# Micro.net
KiCad netlist of a schematic drawn in Altium Designer
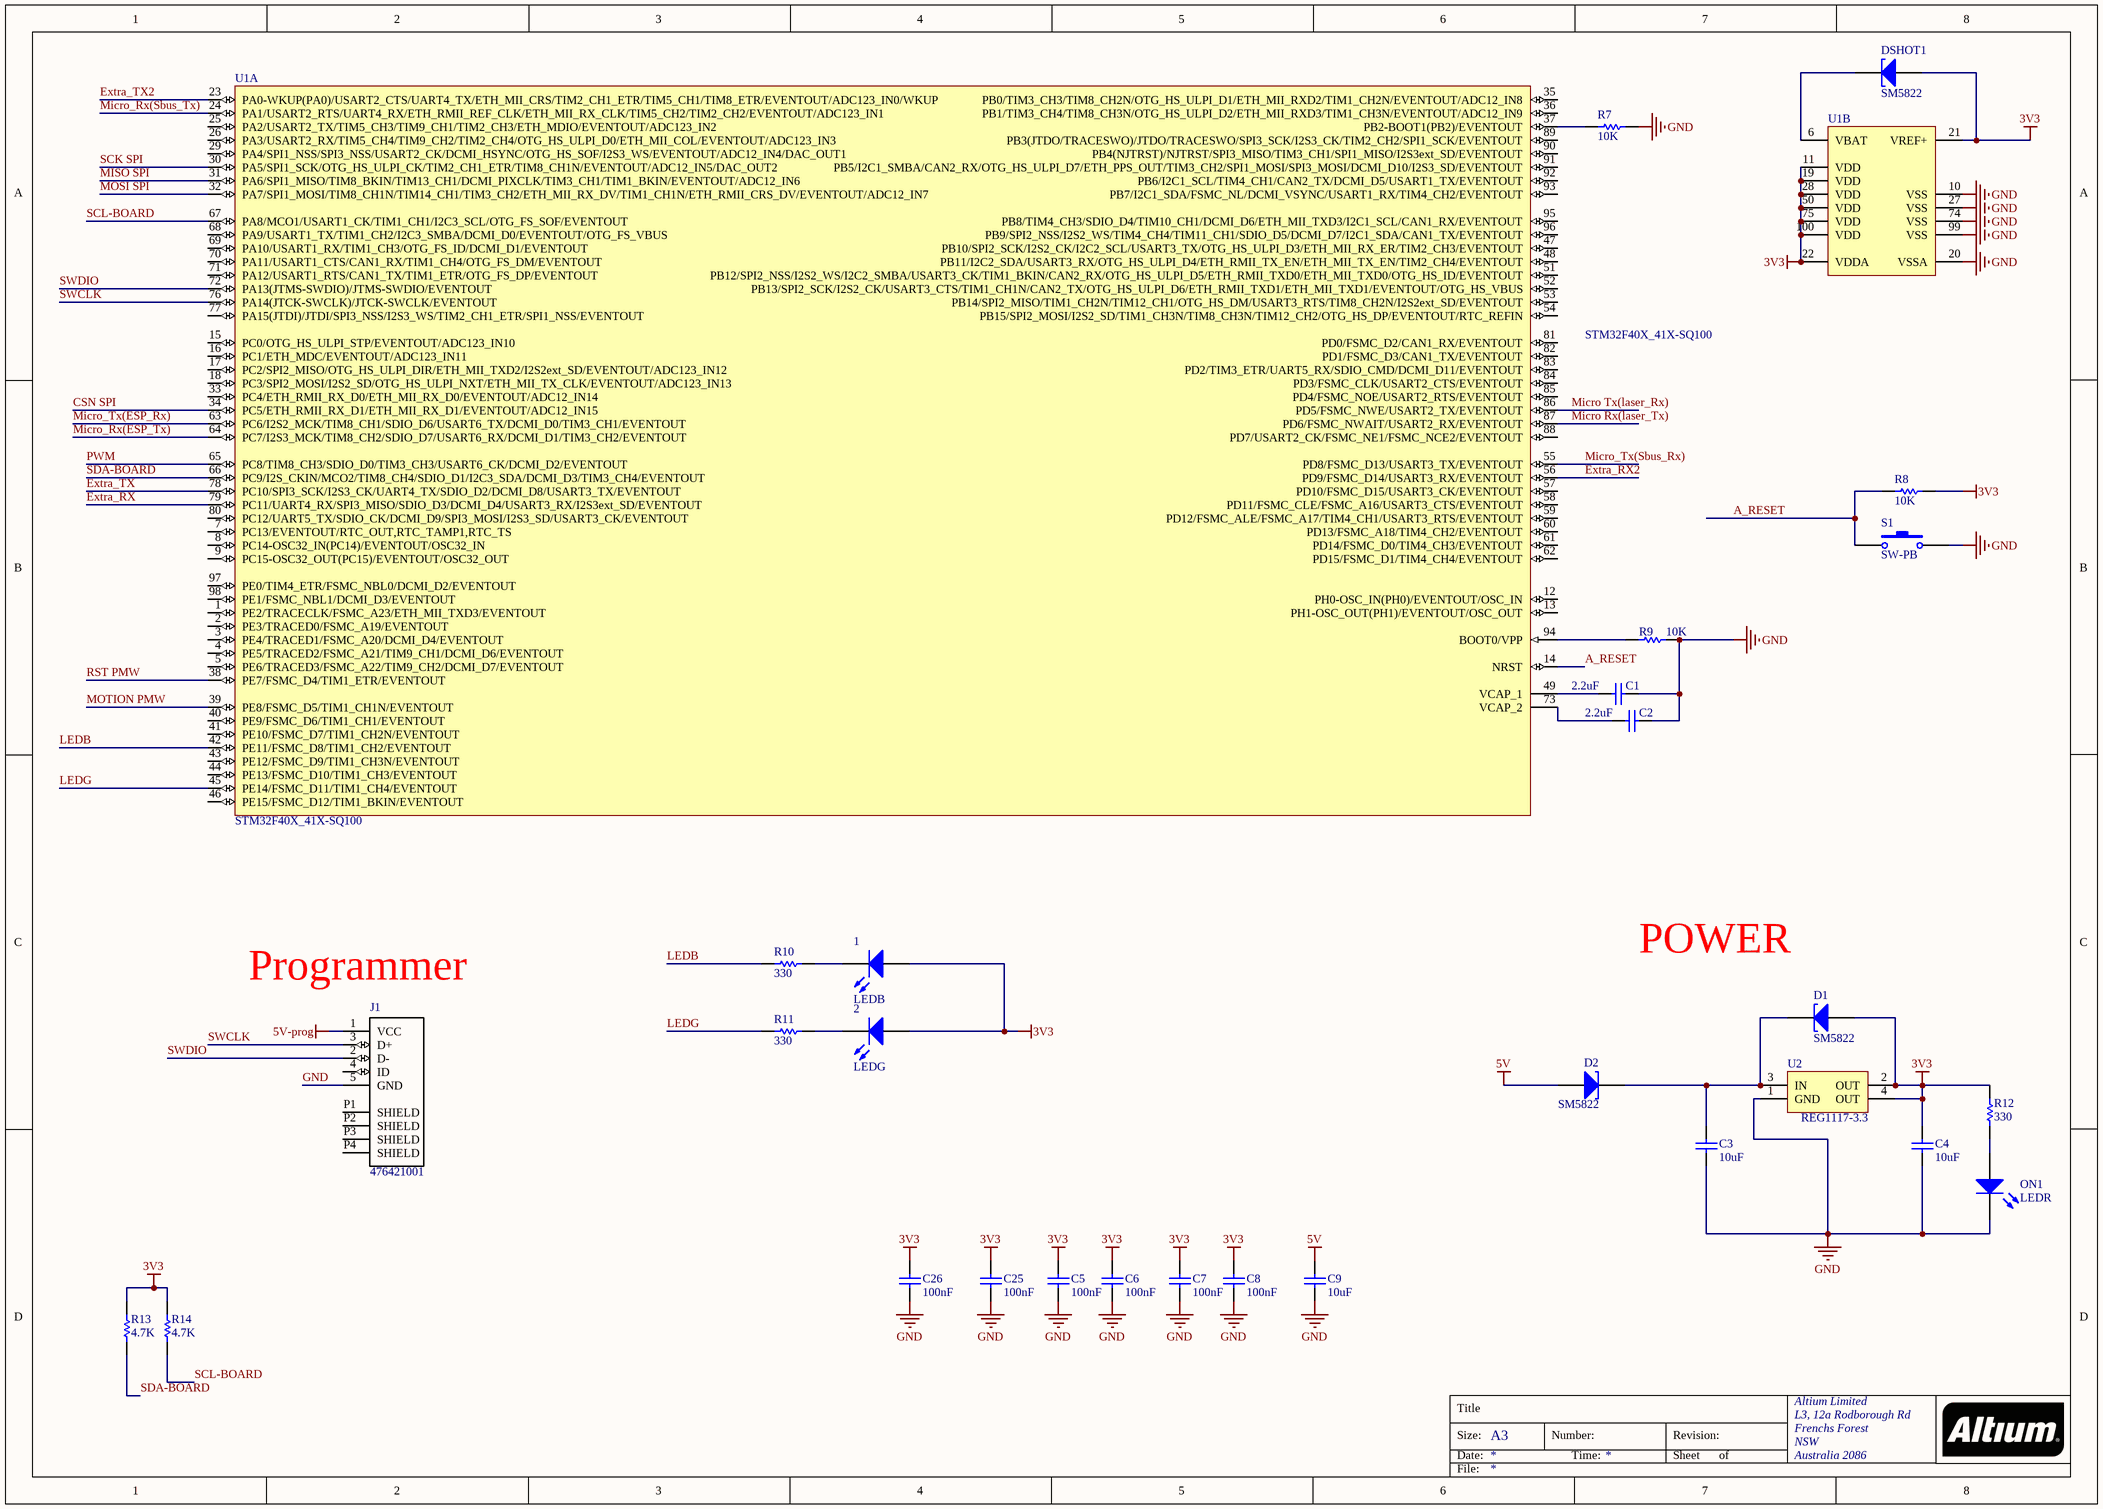
[diagram p0: Micro.SchDoc]

(export (version "E")
  (design (tool "Eeschema 10.0.6"))
  (components
    (comp (ref "1")
      (value "LEDB")
      (footprint "3518")
      (description "Typical INFRARED GaAs LED")
      (fields (field (name "PUBLISHER") "Altium Limited"))
      (libsource (lib "Miscellaneous Devices") (part "LED0"))
    )
    (comp (ref "2")
      (value "LEDG")
      (footprint "3518")
      (description "Typical INFRARED GaAs LED")
      (fields (field (name "PUBLISHER") "Altium Limited"))
      (libsource (lib "Miscellaneous Devices") (part "LED0"))
    )
    (comp (ref "C1")
      (value "2.2uF")
      (footprint "j1-0603")
      (description "Capacitor")
      (fields (field (name "PUBLISHER") "Altium Limited"))
      (libsource (lib "KN2CLib") (part "Cap_UP"))
    )
    (comp (ref "C2")
      (value "2.2uF")
      (footprint "j1-0603")
      (description "Capacitor")
      (fields (field (name "PUBLISHER") "Altium Limited"))
      (libsource (lib "KN2CLib") (part "Cap_UP"))
    )
    (comp (ref "C3")
      (value "10uF")
      (footprint "J1-0603")
      (description "Capacitor")
      (fields (field (name "PUBLISHER") "Altium Limited"))
      (libsource (lib "Miscellaneous Devices") (part "Cap"))
    )
    (comp (ref "C4")
      (value "10uF")
      (footprint "J1-0603")
      (description "Capacitor")
      (fields (field (name "PUBLISHER") "Altium Limited"))
      (libsource (lib "Miscellaneous Devices") (part "Cap"))
    )
    (comp (ref "C5")
      (value "100nF")
      (footprint "j1-0603")
      (description "Capacitor")
      (fields (field (name "PUBLISHER") "Altium Limited"))
      (libsource (lib "Miscellaneous Devices") (part "Cap"))
    )
    (comp (ref "C6")
      (value "100nF")
      (footprint "J1-0603")
      (description "Capacitor")
      (fields (field (name "PUBLISHER") "Altium Limited"))
      (libsource (lib "Miscellaneous Devices") (part "Cap"))
    )
    (comp (ref "C7")
      (value "100nF")
      (footprint "j1-0603")
      (description "Capacitor")
      (fields (field (name "PUBLISHER") "Altium Limited"))
      (libsource (lib "Miscellaneous Devices") (part "Cap"))
    )
    (comp (ref "C8")
      (value "100nF")
      (footprint "J1-0603")
      (description "Capacitor")
      (fields (field (name "PUBLISHER") "Altium Limited"))
      (libsource (lib "Miscellaneous Devices") (part "Cap"))
    )
    (comp (ref "C9")
      (value "10uF")
      (footprint "j1-0603")
      (description "Capacitor")
      (fields (field (name "PUBLISHER") "Altium Limited"))
      (libsource (lib "Miscellaneous Devices") (part "Cap"))
    )
    (comp (ref "C25")
      (value "100nF")
      (footprint "j1-0603")
      (description "Capacitor")
      (fields (field (name "PUBLISHER") "Altium Limited"))
      (libsource (lib "Miscellaneous Devices") (part "Cap"))
    )
    (comp (ref "C26")
      (value "100nF")
      (footprint "j1-0603")
      (description "Capacitor")
      (fields (field (name "PUBLISHER") "Altium Limited"))
      (libsource (lib "Miscellaneous Devices") (part "Cap"))
    )
    (comp (ref "D1")
      (value "SM5822")
      (footprint "US1M")
      (description "1 Amp General Purpose Rectifier")
      (fields (field (name "PUBLISHER") "Altium Limited"))
      (libsource (lib "KN2CLib") (part "Diode_ShotKey"))
    )
    (comp (ref "D2")
      (value "SM5822")
      (footprint "US1M")
      (description "1 Amp General Purpose Rectifier")
      (fields (field (name "PUBLISHER") "Altium Limited"))
      (libsource (lib "KN2CLib") (part "Diode_ShotKey"))
    )
    (comp (ref "DSHOT1")
      (value "SM5822")
      (footprint "US1M")
      (description "1 Amp General Purpose Rectifier")
      (fields (field (name "PUBLISHER") "Altium Limited"))
      (libsource (lib "KN2CLib") (part "Diode_ShotKey"))
    )
    (comp (ref "J1")
      (value "476421001")
      (footprint "*MOLEX_476421001_476421001(Primary)")
      (fields (field (name "MF") "Molex"))
      (libsource (lib "476421001") (part "476421001"))
    )
    (comp (ref "ON1")
      (value "LEDR")
      (footprint "3518")
      (description "Typical INFRARED GaAs LED")
      (fields (field (name "PUBLISHER") "Altium Limited"))
      (libsource (lib "Miscellaneous Devices") (part "LED0"))
    )
    (comp (ref "R7")
      (value "10K")
      (footprint "j1-0603")
      (description "Resistor")
      (fields (field (name "PUBLISHER") "Altium Limited"))
      (libsource (lib "Miscellaneous Devices") (part "Res1"))
    )
    (comp (ref "R8")
      (value "10K")
      (footprint "j1-0603")
      (description "Resistor")
      (fields (field (name "PUBLISHER") "Altium Limited"))
      (libsource (lib "Miscellaneous Devices") (part "Res1"))
    )
    (comp (ref "R9")
      (value "10K")
      (footprint "j1-0603")
      (description "Semiconductor Resistor")
      (fields (field (name "PUBLISHER") "Altium Limited"))
      (libsource (lib "KN2CLib") (part "Res"))
    )
    (comp (ref "R10")
      (value "330")
      (footprint "j1-0603")
      (description "Resistor")
      (fields (field (name "PUBLISHER") "Altium Limited"))
      (libsource (lib "Miscellaneous Devices") (part "Res1"))
    )
    (comp (ref "R11")
      (value "330")
      (footprint "j1-0603")
      (description "Resistor")
      (fields (field (name "PUBLISHER") "Altium Limited"))
      (libsource (lib "Miscellaneous Devices") (part "Res1"))
    )
    (comp (ref "R12")
      (value "330")
      (footprint "J1-0603")
      (description "Resistor")
      (fields (field (name "PUBLISHER") "Altium Limited"))
      (libsource (lib "Miscellaneous Devices") (part "Res1"))
    )
    (comp (ref "R13")
      (value "4.7K")
      (footprint "j1-0603")
      (description "Resistor")
      (fields (field (name "PUBLISHER") "Altium Limited"))
      (libsource (lib "Miscellaneous Devices") (part "Res1"))
    )
    (comp (ref "R14")
      (value "4.7K")
      (footprint "j1-0603")
      (description "Resistor")
      (fields (field (name "PUBLISHER") "Altium Limited"))
      (libsource (lib "Miscellaneous Devices") (part "Res1"))
    )
    (comp (ref "S1")
      (value "SW-PB")
      (footprint "SW-PB-4P")
      (description "Switch")
      (fields (field (name "PUBLISHER") "Altium Limited"))
      (libsource (lib "Miscellaneous Devices") (part "SW-PB"))
    )
    (comp (ref "U1")
      (value "STM32F40X_41X-SQ100")
      (footprint "100A_N")
      (libsource (lib "KN2CLib") (part "STM32F40X_41X-SQ100"))
    )
    (comp (ref "U2")
      (value "REG1117-3.3")
      (footprint "SOT223")
      (description "800mA and 1A Low Dropout Positive Regulator 2.85V, 3.3V, 5V, and Adjustable")
      (fields (field (name "PUBLISHER") "Altium Limited"))
      (libsource (lib "BB Power Mgt Voltage Regulator") (part "REG1117-3.3"))
    )
  )
  (nets
    (net (code "1") (name "/A_RESET") (class "Default")
      (node (ref "R8") (pin "2") (pinfunction "2_2") (pintype "passive"))
      (node (ref "S1") (pin "1") (pinfunction "1_1") (pintype "passive"))
      (node (ref "U1") (pin "14") (pinfunction "NRST_14") (pintype "bidirectional"))
    )
    (net (code "2") (name "/CSN SPI") (class "Default")
      (node (ref "U1") (pin "34") (pinfunction "PC5/ETH_RMII_RX_D1/ETH_MII_RX_D1/EVENTOUT/ADC12_IN15_34") (pintype "bidirectional"))
    )
    (net (code "3") (name "/Extra_RX") (class "Default")
      (node (ref "U1") (pin "79") (pinfunction "PC11/UART4_RX/SPI3_MISO/SDIO_D3/DCMI_D4/USART3_RX/I2S3ext_SD/EVENTOUT_79") (pintype "bidirectional"))
    )
    (net (code "4") (name "/Extra_RX2") (class "Default")
      (node (ref "U1") (pin "56") (pinfunction "PD9/FSMC_D14/USART3_RX/EVENTOUT_56") (pintype "bidirectional"))
    )
    (net (code "5") (name "/Extra_TX") (class "Default")
      (node (ref "U1") (pin "78") (pinfunction "PC10/SPI3_SCK/I2S3_CK/UART4_TX/SDIO_D2/DCMI_D8/USART3_TX/EVENTOUT_78") (pintype "bidirectional"))
    )
    (net (code "6") (name "/Extra_TX2") (class "Default")
      (node (ref "U1") (pin "23") (pinfunction "PA0-WKUP(PA0)/USART2_CTS/UART4_TX/ETH_MII_CRS/TIM2_CH1_ETR/TIM5_CH1/TIM8_ETR/EVENTOUT/ADC123_IN0/WKUP_23") (pintype "bidirectional"))
    )
    (net (code "7") (name "/LEDB") (class "Default")
      (node (ref "R10") (pin "2") (pinfunction "2_2") (pintype "passive"))
      (node (ref "U1") (pin "42") (pinfunction "PE11/FSMC_D8/TIM1_CH2/EVENTOUT_42") (pintype "bidirectional"))
    )
    (net (code "8") (name "/LEDG") (class "Default")
      (node (ref "R11") (pin "2") (pinfunction "2_2") (pintype "passive"))
      (node (ref "U1") (pin "45") (pinfunction "PE14/FSMC_D11/TIM1_CH4/EVENTOUT_45") (pintype "bidirectional"))
    )
    (net (code "9") (name "/MISO SPI") (class "Default")
      (node (ref "U1") (pin "31") (pinfunction "PA6/SPI1_MISO/TIM8_BKIN/TIM13_CH1/DCMI_PIXCLK/TIM3_CH1/TIM1_BKIN/EVENTOUT/ADC12_IN6_31") (pintype "bidirectional"))
    )
    (net (code "10") (name "/MOSI SPI") (class "Default")
      (node (ref "U1") (pin "32") (pinfunction "PA7/SPI1_MOSI/TIM8_CH1N/TIM14_CH1/TIM3_CH2/ETH_MII_RX_DV/TIM1_CH1N/ETH_RMII_CRS_DV/EVENTOUT/ADC12_IN7_32") (pintype "bidirectional"))
    )
    (net (code "11") (name "/MOTION PMW") (class "Default")
      (node (ref "U1") (pin "39") (pinfunction "PE8/FSMC_D5/TIM1_CH1N/EVENTOUT_39") (pintype "bidirectional"))
    )
    (net (code "12") (name "/Micro Rx(laser_Tx)") (class "Default")
      (node (ref "U1") (pin "87") (pinfunction "PD6/FSMC_NWAIT/USART2_RX/EVENTOUT_87") (pintype "bidirectional"))
    )
    (net (code "13") (name "/Micro Tx(laser_Rx)") (class "Default")
      (node (ref "U1") (pin "86") (pinfunction "PD5/FSMC_NWE/USART2_TX/EVENTOUT_86") (pintype "bidirectional"))
    )
    (net (code "14") (name "/Micro_Rx(ESP_Tx)") (class "Default")
      (node (ref "U1") (pin "64") (pinfunction "PC7/I2S3_MCK/TIM8_CH2/SDIO_D7/USART6_RX/DCMI_D1/TIM3_CH2/EVENTOUT_64") (pintype "bidirectional"))
    )
    (net (code "15") (name "/Micro_Rx(Sbus_Tx)") (class "Default")
      (node (ref "U1") (pin "24") (pinfunction "PA1/USART2_RTS/UART4_RX/ETH_RMII_REF_CLK/ETH_MII_RX_CLK/TIM5_CH2/TIM2_CH2/EVENTOUT/ADC123_IN1_24") (pintype "bidirectional"))
    )
    (net (code "16") (name "/Micro_Tx(ESP_Rx)") (class "Default")
      (node (ref "U1") (pin "63") (pinfunction "PC6/I2S2_MCK/TIM8_CH1/SDIO_D6/USART6_TX/DCMI_D0/TIM3_CH1/EVENTOUT_63") (pintype "bidirectional"))
    )
    (net (code "17") (name "/Micro_Tx(Sbus_Rx)") (class "Default")
      (node (ref "U1") (pin "55") (pinfunction "PD8/FSMC_D13/USART3_TX/EVENTOUT_55") (pintype "bidirectional"))
    )
    (net (code "18") (name "/PWM") (class "Default")
      (node (ref "U1") (pin "65") (pinfunction "PC8/TIM8_CH3/SDIO_D0/TIM3_CH3/USART6_CK/DCMI_D2/EVENTOUT_65") (pintype "bidirectional"))
    )
    (net (code "19") (name "/RST PMW") (class "Default")
      (node (ref "U1") (pin "38") (pinfunction "PE7/FSMC_D4/TIM1_ETR/EVENTOUT_38") (pintype "bidirectional"))
    )
    (net (code "20") (name "/SCK SPI") (class "Default")
      (node (ref "U1") (pin "30") (pinfunction "PA5/SPI1_SCK/OTG_HS_ULPI_CK/TIM2_CH1_ETR/TIM8_CH1N/EVENTOUT/ADC12_IN5/DAC_OUT2_30") (pintype "bidirectional"))
    )
    (net (code "21") (name "/SCL-BOARD") (class "Default")
      (node (ref "R14") (pin "2") (pinfunction "2_2") (pintype "passive"))
      (node (ref "U1") (pin "67") (pinfunction "PA8/MCO1/USART1_CK/TIM1_CH1/I2C3_SCL/OTG_FS_SOF/EVENTOUT_67") (pintype "bidirectional"))
    )
    (net (code "22") (name "/SDA-BOARD") (class "Default")
      (node (ref "R13") (pin "2") (pinfunction "2_2") (pintype "passive"))
      (node (ref "U1") (pin "66") (pinfunction "PC9/I2S_CKIN/MCO2/TIM8_CH4/SDIO_D1/I2C3_SDA/DCMI_D3/TIM3_CH4/EVENTOUT_66") (pintype "bidirectional"))
    )
    (net (code "23") (name "/SWCLK") (class "Default")
      (node (ref "J1") (pin "3") (pinfunction "D+_3") (pintype "bidirectional"))
      (node (ref "U1") (pin "76") (pinfunction "PA14(JTCK-SWCLK)/JTCK-SWCLK/EVENTOUT_76") (pintype "bidirectional"))
    )
    (net (code "24") (name "/SWDIO") (class "Default")
      (node (ref "J1") (pin "2") (pinfunction "D-_2") (pintype "bidirectional"))
      (node (ref "U1") (pin "72") (pinfunction "PA13(JTMS-SWDIO)/JTMS-SWDIO/EVENTOUT_72") (pintype "bidirectional"))
    )
    (net (code "25") (name "3V3") (class "Default")
      (node (ref "1") (pin "1") (pinfunction "A_1") (pintype "passive"))
      (node (ref "2") (pin "1") (pinfunction "A_1") (pintype "passive"))
      (node (ref "C25") (pin "2") (pinfunction "2_2") (pintype "passive"))
      (node (ref "C26") (pin "2") (pinfunction "2_2") (pintype "passive"))
      (node (ref "C4") (pin "2") (pinfunction "2_2") (pintype "passive"))
      (node (ref "C5") (pin "2") (pinfunction "2_2") (pintype "passive"))
      (node (ref "C6") (pin "2") (pinfunction "2_2") (pintype "passive"))
      (node (ref "C7") (pin "2") (pinfunction "2_2") (pintype "passive"))
      (node (ref "C8") (pin "2") (pinfunction "2_2") (pintype "passive"))
      (node (ref "D1") (pin "2") (pinfunction "A_2") (pintype "passive"))
      (node (ref "DSHOT1") (pin "2") (pinfunction "A_2") (pintype "passive"))
      (node (ref "R12") (pin "2") (pinfunction "2_2") (pintype "passive"))
      (node (ref "R13") (pin "1") (pinfunction "1_1") (pintype "passive"))
      (node (ref "R14") (pin "1") (pinfunction "1_1") (pintype "passive"))
      (node (ref "R8") (pin "1") (pinfunction "1_1") (pintype "passive"))
      (node (ref "U1") (pin "100") (pinfunction "VDD_100") (pintype "power_in"))
      (node (ref "U1") (pin "11") (pinfunction "VDD_11") (pintype "power_in"))
      (node (ref "U1") (pin "19") (pinfunction "VDD_19") (pintype "power_in"))
      (node (ref "U1") (pin "21") (pinfunction "VREF+_21") (pintype "power_in"))
      (node (ref "U1") (pin "22") (pinfunction "VDDA_22") (pintype "power_in"))
      (node (ref "U1") (pin "28") (pinfunction "VDD_28") (pintype "power_in"))
      (node (ref "U1") (pin "50") (pinfunction "VDD_50") (pintype "power_in"))
      (node (ref "U1") (pin "75") (pinfunction "VDD_75") (pintype "power_in"))
      (node (ref "U2") (pin "2") (pinfunction "OUT_2") (pintype "power_in"))
      (node (ref "U2") (pin "4") (pinfunction "OUT_4") (pintype "power_in"))
    )
    (net (code "26") (name "5V") (class "Default")
      (node (ref "C9") (pin "2") (pinfunction "2_2") (pintype "passive"))
      (node (ref "D2") (pin "2") (pinfunction "A_2") (pintype "passive"))
    )
    (net (code "27") (name "5V-prog") (class "Default")
      (node (ref "J1") (pin "1") (pinfunction "VCC_1") (pintype "power_in"))
    )
    (net (code "28") (name "GND") (class "Default")
      (node (ref "C1") (pin "2") (pinfunction "2_2") (pintype "passive"))
      (node (ref "C2") (pin "2") (pinfunction "2_2") (pintype "passive"))
      (node (ref "C25") (pin "1") (pinfunction "1_1") (pintype "passive"))
      (node (ref "C26") (pin "1") (pinfunction "1_1") (pintype "passive"))
      (node (ref "C3") (pin "1") (pinfunction "1_1") (pintype "passive"))
      (node (ref "C4") (pin "1") (pinfunction "1_1") (pintype "passive"))
      (node (ref "C5") (pin "1") (pinfunction "1_1") (pintype "passive"))
      (node (ref "C6") (pin "1") (pinfunction "1_1") (pintype "passive"))
      (node (ref "C7") (pin "1") (pinfunction "1_1") (pintype "passive"))
      (node (ref "C8") (pin "1") (pinfunction "1_1") (pintype "passive"))
      (node (ref "C9") (pin "1") (pinfunction "1_1") (pintype "passive"))
      (node (ref "J1") (pin "5") (pinfunction "GND_5") (pintype "power_in"))
      (node (ref "ON1") (pin "2") (pinfunction "K_2") (pintype "passive"))
      (node (ref "R7") (pin "1") (pinfunction "1_1") (pintype "passive"))
      (node (ref "R9") (pin "2") (pinfunction "2_2") (pintype "passive"))
      (node (ref "S1") (pin "2") (pinfunction "2_2") (pintype "passive"))
      (node (ref "U1") (pin "10") (pinfunction "VSS_10") (pintype "power_in"))
      (node (ref "U1") (pin "20") (pinfunction "VSSA_20") (pintype "power_in"))
      (node (ref "U1") (pin "27") (pinfunction "VSS_27") (pintype "power_in"))
      (node (ref "U1") (pin "74") (pinfunction "VSS_74") (pintype "power_in"))
      (node (ref "U1") (pin "99") (pinfunction "VSS_99") (pintype "power_in"))
      (node (ref "U2") (pin "1") (pinfunction "GND_1") (pintype "power_in"))
    )
    (net (code "29") (name "Net-(1-K)") (class "Default")
      (node (ref "1") (pin "2") (pinfunction "K_2") (pintype "passive"))
      (node (ref "R10") (pin "1") (pinfunction "1_1") (pintype "passive"))
    )
    (net (code "30") (name "Net-(2-K)") (class "Default")
      (node (ref "2") (pin "2") (pinfunction "K_2") (pintype "passive"))
      (node (ref "R11") (pin "1") (pinfunction "1_1") (pintype "passive"))
    )
    (net (code "31") (name "Net-(D1-K)") (class "Default")
      (node (ref "C3") (pin "2") (pinfunction "2_2") (pintype "passive"))
      (node (ref "D1") (pin "1") (pinfunction "K_1") (pintype "passive"))
      (node (ref "D2") (pin "1") (pinfunction "K_1") (pintype "passive"))
      (node (ref "U2") (pin "3") (pinfunction "IN_3") (pintype "power_in"))
    )
    (net (code "32") (name "Net-(DSHOT1-K)") (class "Default")
      (node (ref "DSHOT1") (pin "1") (pinfunction "K_1") (pintype "passive"))
      (node (ref "U1") (pin "6") (pinfunction "VBAT_6") (pintype "power_in"))
    )
    (net (code "33") (name "Net-(ON1-A)") (class "Default")
      (node (ref "ON1") (pin "1") (pinfunction "A_1") (pintype "passive"))
      (node (ref "R12") (pin "1") (pinfunction "1_1") (pintype "passive"))
    )
    (net (code "34") (name "Net-(U1A-BOOT0{slash}VPP)") (class "Default")
      (node (ref "R9") (pin "1") (pinfunction "1_1") (pintype "passive"))
      (node (ref "U1") (pin "94") (pinfunction "BOOT0/VPP_94") (pintype "input"))
    )
    (net (code "35") (name "Net-(U1A-PB2-BOOT1(PB2){slash}EVENTOUT)") (class "Default")
      (node (ref "R7") (pin "2") (pinfunction "2_2") (pintype "passive"))
      (node (ref "U1") (pin "37") (pinfunction "PB2-BOOT1(PB2)/EVENTOUT_37") (pintype "bidirectional"))
    )
    (net (code "36") (name "Net-(U1A-VCAP_1)") (class "Default")
      (node (ref "C1") (pin "1") (pinfunction "1_1") (pintype "passive"))
      (node (ref "U1") (pin "49") (pinfunction "VCAP_1_49") (pintype "power_in"))
    )
    (net (code "37") (name "Net-(U1A-VCAP_2)") (class "Default")
      (node (ref "C2") (pin "1") (pinfunction "1_1") (pintype "passive"))
      (node (ref "U1") (pin "73") (pinfunction "VCAP_2_73") (pintype "power_in"))
    )
    (net (code "38") (name "unconnected-(J1-ID-Pad4)") (class "Default")
      (node (ref "J1") (pin "4") (pinfunction "ID_4") (pintype "bidirectional"))
    )
    (net (code "39") (name "unconnected-(J1-SHIELD-PadP1)") (class "Default")
      (node (ref "J1") (pin "P1") (pinfunction "SHIELD_P1") (pintype "power_in"))
    )
    (net (code "40") (name "unconnected-(J1-SHIELD-PadP2)") (class "Default")
      (node (ref "J1") (pin "P2") (pinfunction "SHIELD_P2") (pintype "power_in"))
    )
    (net (code "41") (name "unconnected-(J1-SHIELD-PadP3)") (class "Default")
      (node (ref "J1") (pin "P3") (pinfunction "SHIELD_P3") (pintype "power_in"))
    )
    (net (code "42") (name "unconnected-(J1-SHIELD-PadP4)") (class "Default")
      (node (ref "J1") (pin "P4") (pinfunction "SHIELD_P4") (pintype "power_in"))
    )
    (net (code "43") (name "unconnected-(U1A-PA2{slash}USART2_TX{slash}TIM5_CH3{slash}TIM9_CH1{slash}TIM2_CH3{slash}ETH_MDIO{slash}EVENTOUT{slash}ADC123_IN2-Pad25)") (class "Default")
      (node (ref "U1") (pin "25") (pinfunction "PA2/USART2_TX/TIM5_CH3/TIM9_CH1/TIM2_CH3/ETH_MDIO/EVENTOUT/ADC123_IN2_25") (pintype "bidirectional"))
    )
    (net (code "44") (name "unconnected-(U1A-PA3{slash}USART2_RX{slash}TIM5_CH4{slash}TIM9_CH2{slash}TIM2_CH4{slash}OTG_HS_ULPI_D0{slash}ETH_MII_COL{slash}EVENTOUT{slash}ADC123_IN3-Pad26)") (class "Default")
      (node (ref "U1") (pin "26") (pinfunction "PA3/USART2_RX/TIM5_CH4/TIM9_CH2/TIM2_CH4/OTG_HS_ULPI_D0/ETH_MII_COL/EVENTOUT/ADC123_IN3_26") (pintype "bidirectional"))
    )
    (net (code "45") (name "unconnected-(U1A-PA4{slash}SPI1_NSS{slash}SPI3_NSS{slash}USART2_CK{slash}DCMI_HSYNC{slash}OTG_HS_SOF{slash}I2S3_WS{slash}EVENTOUT{slash}ADC12_IN4{slash}DAC_OUT1-Pad29)") (class "Default")
      (node (ref "U1") (pin "29") (pinfunction "PA4/SPI1_NSS/SPI3_NSS/USART2_CK/DCMI_HSYNC/OTG_HS_SOF/I2S3_WS/EVENTOUT/ADC12_IN4/DAC_OUT1_29") (pintype "bidirectional"))
    )
    (net (code "46") (name "unconnected-(U1A-PA9{slash}USART1_TX{slash}TIM1_CH2{slash}I2C3_SMBA{slash}DCMI_D0{slash}EVENTOUT{slash}OTG_FS_VBUS-Pad68)") (class "Default")
      (node (ref "U1") (pin "68") (pinfunction "PA9/USART1_TX/TIM1_CH2/I2C3_SMBA/DCMI_D0/EVENTOUT/OTG_FS_VBUS_68") (pintype "bidirectional"))
    )
    (net (code "47") (name "unconnected-(U1A-PA10{slash}USART1_RX{slash}TIM1_CH3{slash}OTG_FS_ID{slash}DCMI_D1{slash}EVENTOUT-Pad69)") (class "Default")
      (node (ref "U1") (pin "69") (pinfunction "PA10/USART1_RX/TIM1_CH3/OTG_FS_ID/DCMI_D1/EVENTOUT_69") (pintype "bidirectional"))
    )
    (net (code "48") (name "unconnected-(U1A-PA11{slash}USART1_CTS{slash}CAN1_RX{slash}TIM1_CH4{slash}OTG_FS_DM{slash}EVENTOUT-Pad70)") (class "Default")
      (node (ref "U1") (pin "70") (pinfunction "PA11/USART1_CTS/CAN1_RX/TIM1_CH4/OTG_FS_DM/EVENTOUT_70") (pintype "bidirectional"))
    )
    (net (code "49") (name "unconnected-(U1A-PA12{slash}USART1_RTS{slash}CAN1_TX{slash}TIM1_ETR{slash}OTG_FS_DP{slash}EVENTOUT-Pad71)") (class "Default")
      (node (ref "U1") (pin "71") (pinfunction "PA12/USART1_RTS/CAN1_TX/TIM1_ETR/OTG_FS_DP/EVENTOUT_71") (pintype "bidirectional"))
    )
    (net (code "50") (name "unconnected-(U1A-PA15(JTDI){slash}JTDI{slash}SPI3_NSS{slash}I2S3_WS{slash}TIM2_CH1_ETR{slash}SPI1_NSS{slash}EVENTOUT-Pad77)") (class "Default")
      (node (ref "U1") (pin "77") (pinfunction "PA15(JTDI)/JTDI/SPI3_NSS/I2S3_WS/TIM2_CH1_ETR/SPI1_NSS/EVENTOUT_77") (pintype "bidirectional"))
    )
    (net (code "51") (name "unconnected-(U1A-PB0{slash}TIM3_CH3{slash}TIM8_CH2N{slash}OTG_HS_ULPI_D1{slash}ETH_MII_RXD2{slash}TIM1_CH2N{slash}EVENTOUT{slash}ADC12_IN8-Pad35)") (class "Default")
      (node (ref "U1") (pin "35") (pinfunction "PB0/TIM3_CH3/TIM8_CH2N/OTG_HS_ULPI_D1/ETH_MII_RXD2/TIM1_CH2N/EVENTOUT/ADC12_IN8_35") (pintype "bidirectional"))
    )
    (net (code "52") (name "unconnected-(U1A-PB1{slash}TIM3_CH4{slash}TIM8_CH3N{slash}OTG_HS_ULPI_D2{slash}ETH_MII_RXD3{slash}TIM1_CH3N{slash}EVENTOUT{slash}ADC12_IN9-Pad36)") (class "Default")
      (node (ref "U1") (pin "36") (pinfunction "PB1/TIM3_CH4/TIM8_CH3N/OTG_HS_ULPI_D2/ETH_MII_RXD3/TIM1_CH3N/EVENTOUT/ADC12_IN9_36") (pintype "bidirectional"))
    )
    (net (code "53") (name "unconnected-(U1A-PB3(JTDO{slash}TRACESWO){slash}JTDO{slash}TRACESWO{slash}SPI3_SCK{slash}I2S3_CK{slash}TIM2_CH2{slash}SPI1_SCK{slash}EVENTOUT-Pad89)") (class "Default")
      (node (ref "U1") (pin "89") (pinfunction "PB3(JTDO/TRACESWO)/JTDO/TRACESWO/SPI3_SCK/I2S3_CK/TIM2_CH2/SPI1_SCK/EVENTOUT_89") (pintype "bidirectional"))
    )
    (net (code "54") (name "unconnected-(U1A-PB4(NJTRST){slash}NJTRST{slash}SPI3_MISO{slash}TIM3_CH1{slash}SPI1_MISO{slash}I2S3ext_SD{slash}EVENTOUT-Pad90)") (class "Default")
      (node (ref "U1") (pin "90") (pinfunction "PB4(NJTRST)/NJTRST/SPI3_MISO/TIM3_CH1/SPI1_MISO/I2S3ext_SD/EVENTOUT_90") (pintype "bidirectional"))
    )
    (net (code "55") (name "unconnected-(U1A-PB5{slash}I2C1_SMBA{slash}CAN2_RX{slash}OTG_HS_ULPI_D7{slash}ETH_PPS_OUT{slash}TIM3_CH2{slash}SPI1_MOSI{slash}SPI3_MOSI{slash}DCMI_D10{slash}I2S3_SD{slash}EVENTOUT-Pad91)") (class "Default")
      (node (ref "U1") (pin "91") (pinfunction "PB5/I2C1_SMBA/CAN2_RX/OTG_HS_ULPI_D7/ETH_PPS_OUT/TIM3_CH2/SPI1_MOSI/SPI3_MOSI/DCMI_D10/I2S3_SD/EVENTOUT_91") (pintype "bidirectional"))
    )
    (net (code "56") (name "unconnected-(U1A-PB6{slash}I2C1_SCL{slash}TIM4_CH1{slash}CAN2_TX{slash}DCMI_D5{slash}USART1_TX{slash}EVENTOUT-Pad92)") (class "Default")
      (node (ref "U1") (pin "92") (pinfunction "PB6/I2C1_SCL/TIM4_CH1/CAN2_TX/DCMI_D5/USART1_TX/EVENTOUT_92") (pintype "bidirectional"))
    )
    (net (code "57") (name "unconnected-(U1A-PB7{slash}I2C1_SDA{slash}FSMC_NL{slash}DCMI_VSYNC{slash}USART1_RX{slash}TIM4_CH2{slash}EVENTOUT-Pad93)") (class "Default")
      (node (ref "U1") (pin "93") (pinfunction "PB7/I2C1_SDA/FSMC_NL/DCMI_VSYNC/USART1_RX/TIM4_CH2/EVENTOUT_93") (pintype "bidirectional"))
    )
    (net (code "58") (name "unconnected-(U1A-PB8{slash}TIM4_CH3{slash}SDIO_D4{slash}TIM10_CH1{slash}DCMI_D6{slash}ETH_MII_TXD3{slash}I2C1_SCL{slash}CAN1_RX{slash}EVENTOUT-Pad95)") (class "Default")
      (node (ref "U1") (pin "95") (pinfunction "PB8/TIM4_CH3/SDIO_D4/TIM10_CH1/DCMI_D6/ETH_MII_TXD3/I2C1_SCL/CAN1_RX/EVENTOUT_95") (pintype "bidirectional"))
    )
    (net (code "59") (name "unconnected-(U1A-PB9{slash}SPI2_NSS{slash}I2S2_WS{slash}TIM4_CH4{slash}TIM11_CH1{slash}SDIO_D5{slash}DCMI_D7{slash}I2C1_SDA{slash}CAN1_TX{slash}EVENTOUT-Pad96)") (class "Default")
      (node (ref "U1") (pin "96") (pinfunction "PB9/SPI2_NSS/I2S2_WS/TIM4_CH4/TIM11_CH1/SDIO_D5/DCMI_D7/I2C1_SDA/CAN1_TX/EVENTOUT_96") (pintype "bidirectional"))
    )
    (net (code "60") (name "unconnected-(U1A-PB10{slash}SPI2_SCK{slash}I2S2_CK{slash}I2C2_SCL{slash}USART3_TX{slash}OTG_HS_ULPI_D3{slash}ETH_MII_RX_ER{slash}TIM2_CH3{slash}EVENTOUT-Pad47)") (class "Default")
      (node (ref "U1") (pin "47") (pinfunction "PB10/SPI2_SCK/I2S2_CK/I2C2_SCL/USART3_TX/OTG_HS_ULPI_D3/ETH_MII_RX_ER/TIM2_CH3/EVENTOUT_47") (pintype "bidirectional"))
    )
    (net (code "61") (name "unconnected-(U1A-PB11{slash}I2C2_SDA{slash}USART3_RX{slash}OTG_HS_ULPI_D4{slash}ETH_RMII_TX_EN{slash}ETH_MII_TX_EN{slash}TIM2_CH4{slash}EVENTOUT-Pad48)") (class "Default")
      (node (ref "U1") (pin "48") (pinfunction "PB11/I2C2_SDA/USART3_RX/OTG_HS_ULPI_D4/ETH_RMII_TX_EN/ETH_MII_TX_EN/TIM2_CH4/EVENTOUT_48") (pintype "bidirectional"))
    )
    (net (code "62") (name "unconnected-(U1A-PB12{slash}SPI2_NSS{slash}I2S2_WS{slash}I2C2_SMBA{slash}USART3_CK{slash}TIM1_BKIN{slash}CAN2_RX{slash}OTG_HS_ULPI_D5{slash}ETH_RMII_TXD0{slash}ETH_MII_TXD0{slash}OTG_HS_ID{slash}EVENTOUT-Pad51)") (class "Default")
      (node (ref "U1") (pin "51") (pinfunction "PB12/SPI2_NSS/I2S2_WS/I2C2_SMBA/USART3_CK/TIM1_BKIN/CAN2_RX/OTG_HS_ULPI_D5/ETH_RMII_TXD0/ETH_MII_TXD0/OTG_HS_ID/EVENTOUT_51") (pintype "bidirectional"))
    )
    (net (code "63") (name "unconnected-(U1A-PB13{slash}SPI2_SCK{slash}I2S2_CK{slash}USART3_CTS{slash}TIM1_CH1N{slash}CAN2_TX{slash}OTG_HS_ULPI_D6{slash}ETH_RMII_TXD1{slash}ETH_MII_TXD1{slash}EVENTOUT{slash}OTG_HS_VBUS-Pad52)") (class "Default")
      (node (ref "U1") (pin "52") (pinfunction "PB13/SPI2_SCK/I2S2_CK/USART3_CTS/TIM1_CH1N/CAN2_TX/OTG_HS_ULPI_D6/ETH_RMII_TXD1/ETH_MII_TXD1/EVENTOUT/OTG_HS_VBUS_52") (pintype "bidirectional"))
    )
    (net (code "64") (name "unconnected-(U1A-PB14{slash}SPI2_MISO{slash}TIM1_CH2N{slash}TIM12_CH1{slash}OTG_HS_DM{slash}USART3_RTS{slash}TIM8_CH2N{slash}I2S2ext_SD{slash}EVENTOUT-Pad53)") (class "Default")
      (node (ref "U1") (pin "53") (pinfunction "PB14/SPI2_MISO/TIM1_CH2N/TIM12_CH1/OTG_HS_DM/USART3_RTS/TIM8_CH2N/I2S2ext_SD/EVENTOUT_53") (pintype "bidirectional"))
    )
    (net (code "65") (name "unconnected-(U1A-PB15{slash}SPI2_MOSI{slash}I2S2_SD{slash}TIM1_CH3N{slash}TIM8_CH3N{slash}TIM12_CH2{slash}OTG_HS_DP{slash}EVENTOUT{slash}RTC_REFIN-Pad54)") (class "Default")
      (node (ref "U1") (pin "54") (pinfunction "PB15/SPI2_MOSI/I2S2_SD/TIM1_CH3N/TIM8_CH3N/TIM12_CH2/OTG_HS_DP/EVENTOUT/RTC_REFIN_54") (pintype "bidirectional"))
    )
    (net (code "66") (name "unconnected-(U1A-PC0{slash}OTG_HS_ULPI_STP{slash}EVENTOUT{slash}ADC123_IN10-Pad15)") (class "Default")
      (node (ref "U1") (pin "15") (pinfunction "PC0/OTG_HS_ULPI_STP/EVENTOUT/ADC123_IN10_15") (pintype "bidirectional"))
    )
    (net (code "67") (name "unconnected-(U1A-PC1{slash}ETH_MDC{slash}EVENTOUT{slash}ADC123_IN11-Pad16)") (class "Default")
      (node (ref "U1") (pin "16") (pinfunction "PC1/ETH_MDC/EVENTOUT/ADC123_IN11_16") (pintype "bidirectional"))
    )
    (net (code "68") (name "unconnected-(U1A-PC2{slash}SPI2_MISO{slash}OTG_HS_ULPI_DIR{slash}ETH_MII_TXD2{slash}I2S2ext_SD{slash}EVENTOUT{slash}ADC123_IN12-Pad17)") (class "Default")
      (node (ref "U1") (pin "17") (pinfunction "PC2/SPI2_MISO/OTG_HS_ULPI_DIR/ETH_MII_TXD2/I2S2ext_SD/EVENTOUT/ADC123_IN12_17") (pintype "bidirectional"))
    )
    (net (code "69") (name "unconnected-(U1A-PC3{slash}SPI2_MOSI{slash}I2S2_SD{slash}OTG_HS_ULPI_NXT{slash}ETH_MII_TX_CLK{slash}EVENTOUT{slash}ADC123_IN13-Pad18)") (class "Default")
      (node (ref "U1") (pin "18") (pinfunction "PC3/SPI2_MOSI/I2S2_SD/OTG_HS_ULPI_NXT/ETH_MII_TX_CLK/EVENTOUT/ADC123_IN13_18") (pintype "bidirectional"))
    )
    (net (code "70") (name "unconnected-(U1A-PC4{slash}ETH_RMII_RX_D0{slash}ETH_MII_RX_D0{slash}EVENTOUT{slash}ADC12_IN14-Pad33)") (class "Default")
      (node (ref "U1") (pin "33") (pinfunction "PC4/ETH_RMII_RX_D0/ETH_MII_RX_D0/EVENTOUT/ADC12_IN14_33") (pintype "bidirectional"))
    )
    (net (code "71") (name "unconnected-(U1A-PC12{slash}UART5_TX{slash}SDIO_CK{slash}DCMI_D9{slash}SPI3_MOSI{slash}I2S3_SD{slash}USART3_CK{slash}EVENTOUT-Pad80)") (class "Default")
      (node (ref "U1") (pin "80") (pinfunction "PC12/UART5_TX/SDIO_CK/DCMI_D9/SPI3_MOSI/I2S3_SD/USART3_CK/EVENTOUT_80") (pintype "bidirectional"))
    )
    (net (code "72") (name "unconnected-(U1A-PC13{slash}EVENTOUT{slash}RTC_OUT,RTC_TAMP1,RTC_TS-Pad7)") (class "Default")
      (node (ref "U1") (pin "7") (pinfunction "PC13/EVENTOUT/RTC_OUT,RTC_TAMP1,RTC_TS_7") (pintype "bidirectional"))
    )
    (net (code "73") (name "unconnected-(U1A-PC14-OSC32_IN(PC14){slash}EVENTOUT{slash}OSC32_IN-Pad8)") (class "Default")
      (node (ref "U1") (pin "8") (pinfunction "PC14-OSC32_IN(PC14)/EVENTOUT/OSC32_IN_8") (pintype "bidirectional"))
    )
    (net (code "74") (name "unconnected-(U1A-PC15-OSC32_OUT(PC15){slash}EVENTOUT{slash}OSC32_OUT-Pad9)") (class "Default")
      (node (ref "U1") (pin "9") (pinfunction "PC15-OSC32_OUT(PC15)/EVENTOUT/OSC32_OUT_9") (pintype "bidirectional"))
    )
    (net (code "75") (name "unconnected-(U1A-PD0{slash}FSMC_D2{slash}CAN1_RX{slash}EVENTOUT-Pad81)") (class "Default")
      (node (ref "U1") (pin "81") (pinfunction "PD0/FSMC_D2/CAN1_RX/EVENTOUT_81") (pintype "bidirectional"))
    )
    (net (code "76") (name "unconnected-(U1A-PD1{slash}FSMC_D3{slash}CAN1_TX{slash}EVENTOUT-Pad82)") (class "Default")
      (node (ref "U1") (pin "82") (pinfunction "PD1/FSMC_D3/CAN1_TX/EVENTOUT_82") (pintype "bidirectional"))
    )
    (net (code "77") (name "unconnected-(U1A-PD2{slash}TIM3_ETR{slash}UART5_RX{slash}SDIO_CMD{slash}DCMI_D11{slash}EVENTOUT-Pad83)") (class "Default")
      (node (ref "U1") (pin "83") (pinfunction "PD2/TIM3_ETR/UART5_RX/SDIO_CMD/DCMI_D11/EVENTOUT_83") (pintype "bidirectional"))
    )
    (net (code "78") (name "unconnected-(U1A-PD3{slash}FSMC_CLK{slash}USART2_CTS{slash}EVENTOUT-Pad84)") (class "Default")
      (node (ref "U1") (pin "84") (pinfunction "PD3/FSMC_CLK/USART2_CTS/EVENTOUT_84") (pintype "bidirectional"))
    )
    (net (code "79") (name "unconnected-(U1A-PD4{slash}FSMC_NOE{slash}USART2_RTS{slash}EVENTOUT-Pad85)") (class "Default")
      (node (ref "U1") (pin "85") (pinfunction "PD4/FSMC_NOE/USART2_RTS/EVENTOUT_85") (pintype "bidirectional"))
    )
    (net (code "80") (name "unconnected-(U1A-PD7{slash}USART2_CK{slash}FSMC_NE1{slash}FSMC_NCE2{slash}EVENTOUT-Pad88)") (class "Default")
      (node (ref "U1") (pin "88") (pinfunction "PD7/USART2_CK/FSMC_NE1/FSMC_NCE2/EVENTOUT_88") (pintype "bidirectional"))
    )
    (net (code "81") (name "unconnected-(U1A-PD10{slash}FSMC_D15{slash}USART3_CK{slash}EVENTOUT-Pad57)") (class "Default")
      (node (ref "U1") (pin "57") (pinfunction "PD10/FSMC_D15/USART3_CK/EVENTOUT_57") (pintype "bidirectional"))
    )
    (net (code "82") (name "unconnected-(U1A-PD11{slash}FSMC_CLE{slash}FSMC_A16{slash}USART3_CTS{slash}EVENTOUT-Pad58)") (class "Default")
      (node (ref "U1") (pin "58") (pinfunction "PD11/FSMC_CLE/FSMC_A16/USART3_CTS/EVENTOUT_58") (pintype "bidirectional"))
    )
    (net (code "83") (name "unconnected-(U1A-PD12{slash}FSMC_ALE{slash}FSMC_A17{slash}TIM4_CH1{slash}USART3_RTS{slash}EVENTOUT-Pad59)") (class "Default")
      (node (ref "U1") (pin "59") (pinfunction "PD12/FSMC_ALE/FSMC_A17/TIM4_CH1/USART3_RTS/EVENTOUT_59") (pintype "bidirectional"))
    )
    (net (code "84") (name "unconnected-(U1A-PD13{slash}FSMC_A18{slash}TIM4_CH2{slash}EVENTOUT-Pad60)") (class "Default")
      (node (ref "U1") (pin "60") (pinfunction "PD13/FSMC_A18/TIM4_CH2/EVENTOUT_60") (pintype "bidirectional"))
    )
    (net (code "85") (name "unconnected-(U1A-PD14{slash}FSMC_D0{slash}TIM4_CH3{slash}EVENTOUT-Pad61)") (class "Default")
      (node (ref "U1") (pin "61") (pinfunction "PD14/FSMC_D0/TIM4_CH3/EVENTOUT_61") (pintype "bidirectional"))
    )
    (net (code "86") (name "unconnected-(U1A-PD15{slash}FSMC_D1{slash}TIM4_CH4{slash}EVENTOUT-Pad62)") (class "Default")
      (node (ref "U1") (pin "62") (pinfunction "PD15/FSMC_D1/TIM4_CH4/EVENTOUT_62") (pintype "bidirectional"))
    )
    (net (code "87") (name "unconnected-(U1A-PE0{slash}TIM4_ETR{slash}FSMC_NBL0{slash}DCMI_D2{slash}EVENTOUT-Pad97)") (class "Default")
      (node (ref "U1") (pin "97") (pinfunction "PE0/TIM4_ETR/FSMC_NBL0/DCMI_D2/EVENTOUT_97") (pintype "bidirectional"))
    )
    (net (code "88") (name "unconnected-(U1A-PE1{slash}FSMC_NBL1{slash}DCMI_D3{slash}EVENTOUT-Pad98)") (class "Default")
      (node (ref "U1") (pin "98") (pinfunction "PE1/FSMC_NBL1/DCMI_D3/EVENTOUT_98") (pintype "bidirectional"))
    )
    (net (code "89") (name "unconnected-(U1A-PE2{slash}TRACECLK{slash}FSMC_A23{slash}ETH_MII_TXD3{slash}EVENTOUT-Pad1)") (class "Default")
      (node (ref "U1") (pin "1") (pinfunction "PE2/TRACECLK/FSMC_A23/ETH_MII_TXD3/EVENTOUT_1") (pintype "bidirectional"))
    )
    (net (code "90") (name "unconnected-(U1A-PE3{slash}TRACED0{slash}FSMC_A19{slash}EVENTOUT-Pad2)") (class "Default")
      (node (ref "U1") (pin "2") (pinfunction "PE3/TRACED0/FSMC_A19/EVENTOUT_2") (pintype "bidirectional"))
    )
    (net (code "91") (name "unconnected-(U1A-PE4{slash}TRACED1{slash}FSMC_A20{slash}DCMI_D4{slash}EVENTOUT-Pad3)") (class "Default")
      (node (ref "U1") (pin "3") (pinfunction "PE4/TRACED1/FSMC_A20/DCMI_D4/EVENTOUT_3") (pintype "bidirectional"))
    )
    (net (code "92") (name "unconnected-(U1A-PE5{slash}TRACED2{slash}FSMC_A21{slash}TIM9_CH1{slash}DCMI_D6{slash}EVENTOUT-Pad4)") (class "Default")
      (node (ref "U1") (pin "4") (pinfunction "PE5/TRACED2/FSMC_A21/TIM9_CH1/DCMI_D6/EVENTOUT_4") (pintype "bidirectional"))
    )
    (net (code "93") (name "unconnected-(U1A-PE6{slash}TRACED3{slash}FSMC_A22{slash}TIM9_CH2{slash}DCMI_D7{slash}EVENTOUT-Pad5)") (class "Default")
      (node (ref "U1") (pin "5") (pinfunction "PE6/TRACED3/FSMC_A22/TIM9_CH2/DCMI_D7/EVENTOUT_5") (pintype "bidirectional"))
    )
    (net (code "94") (name "unconnected-(U1A-PE9{slash}FSMC_D6{slash}TIM1_CH1{slash}EVENTOUT-Pad40)") (class "Default")
      (node (ref "U1") (pin "40") (pinfunction "PE9/FSMC_D6/TIM1_CH1/EVENTOUT_40") (pintype "bidirectional"))
    )
    (net (code "95") (name "unconnected-(U1A-PE10{slash}FSMC_D7{slash}TIM1_CH2N{slash}EVENTOUT-Pad41)") (class "Default")
      (node (ref "U1") (pin "41") (pinfunction "PE10/FSMC_D7/TIM1_CH2N/EVENTOUT_41") (pintype "bidirectional"))
    )
    (net (code "96") (name "unconnected-(U1A-PE12{slash}FSMC_D9{slash}TIM1_CH3N{slash}EVENTOUT-Pad43)") (class "Default")
      (node (ref "U1") (pin "43") (pinfunction "PE12/FSMC_D9/TIM1_CH3N/EVENTOUT_43") (pintype "bidirectional"))
    )
    (net (code "97") (name "unconnected-(U1A-PE13{slash}FSMC_D10{slash}TIM1_CH3{slash}EVENTOUT-Pad44)") (class "Default")
      (node (ref "U1") (pin "44") (pinfunction "PE13/FSMC_D10/TIM1_CH3/EVENTOUT_44") (pintype "bidirectional"))
    )
    (net (code "98") (name "unconnected-(U1A-PE15{slash}FSMC_D12{slash}TIM1_BKIN{slash}EVENTOUT-Pad46)") (class "Default")
      (node (ref "U1") (pin "46") (pinfunction "PE15/FSMC_D12/TIM1_BKIN/EVENTOUT_46") (pintype "bidirectional"))
    )
    (net (code "99") (name "unconnected-(U1A-PH0-OSC_IN(PH0){slash}EVENTOUT{slash}OSC_IN-Pad12)") (class "Default")
      (node (ref "U1") (pin "12") (pinfunction "PH0-OSC_IN(PH0)/EVENTOUT/OSC_IN_12") (pintype "bidirectional"))
    )
    (net (code "100") (name "unconnected-(U1A-PH1-OSC_OUT(PH1){slash}EVENTOUT{slash}OSC_OUT-Pad13)") (class "Default")
      (node (ref "U1") (pin "13") (pinfunction "PH1-OSC_OUT(PH1)/EVENTOUT/OSC_OUT_13") (pintype "bidirectional"))
    )
  )
)
